# BasicSAMD21.net
KiCad netlist of a schematic drawn in Altium Designer
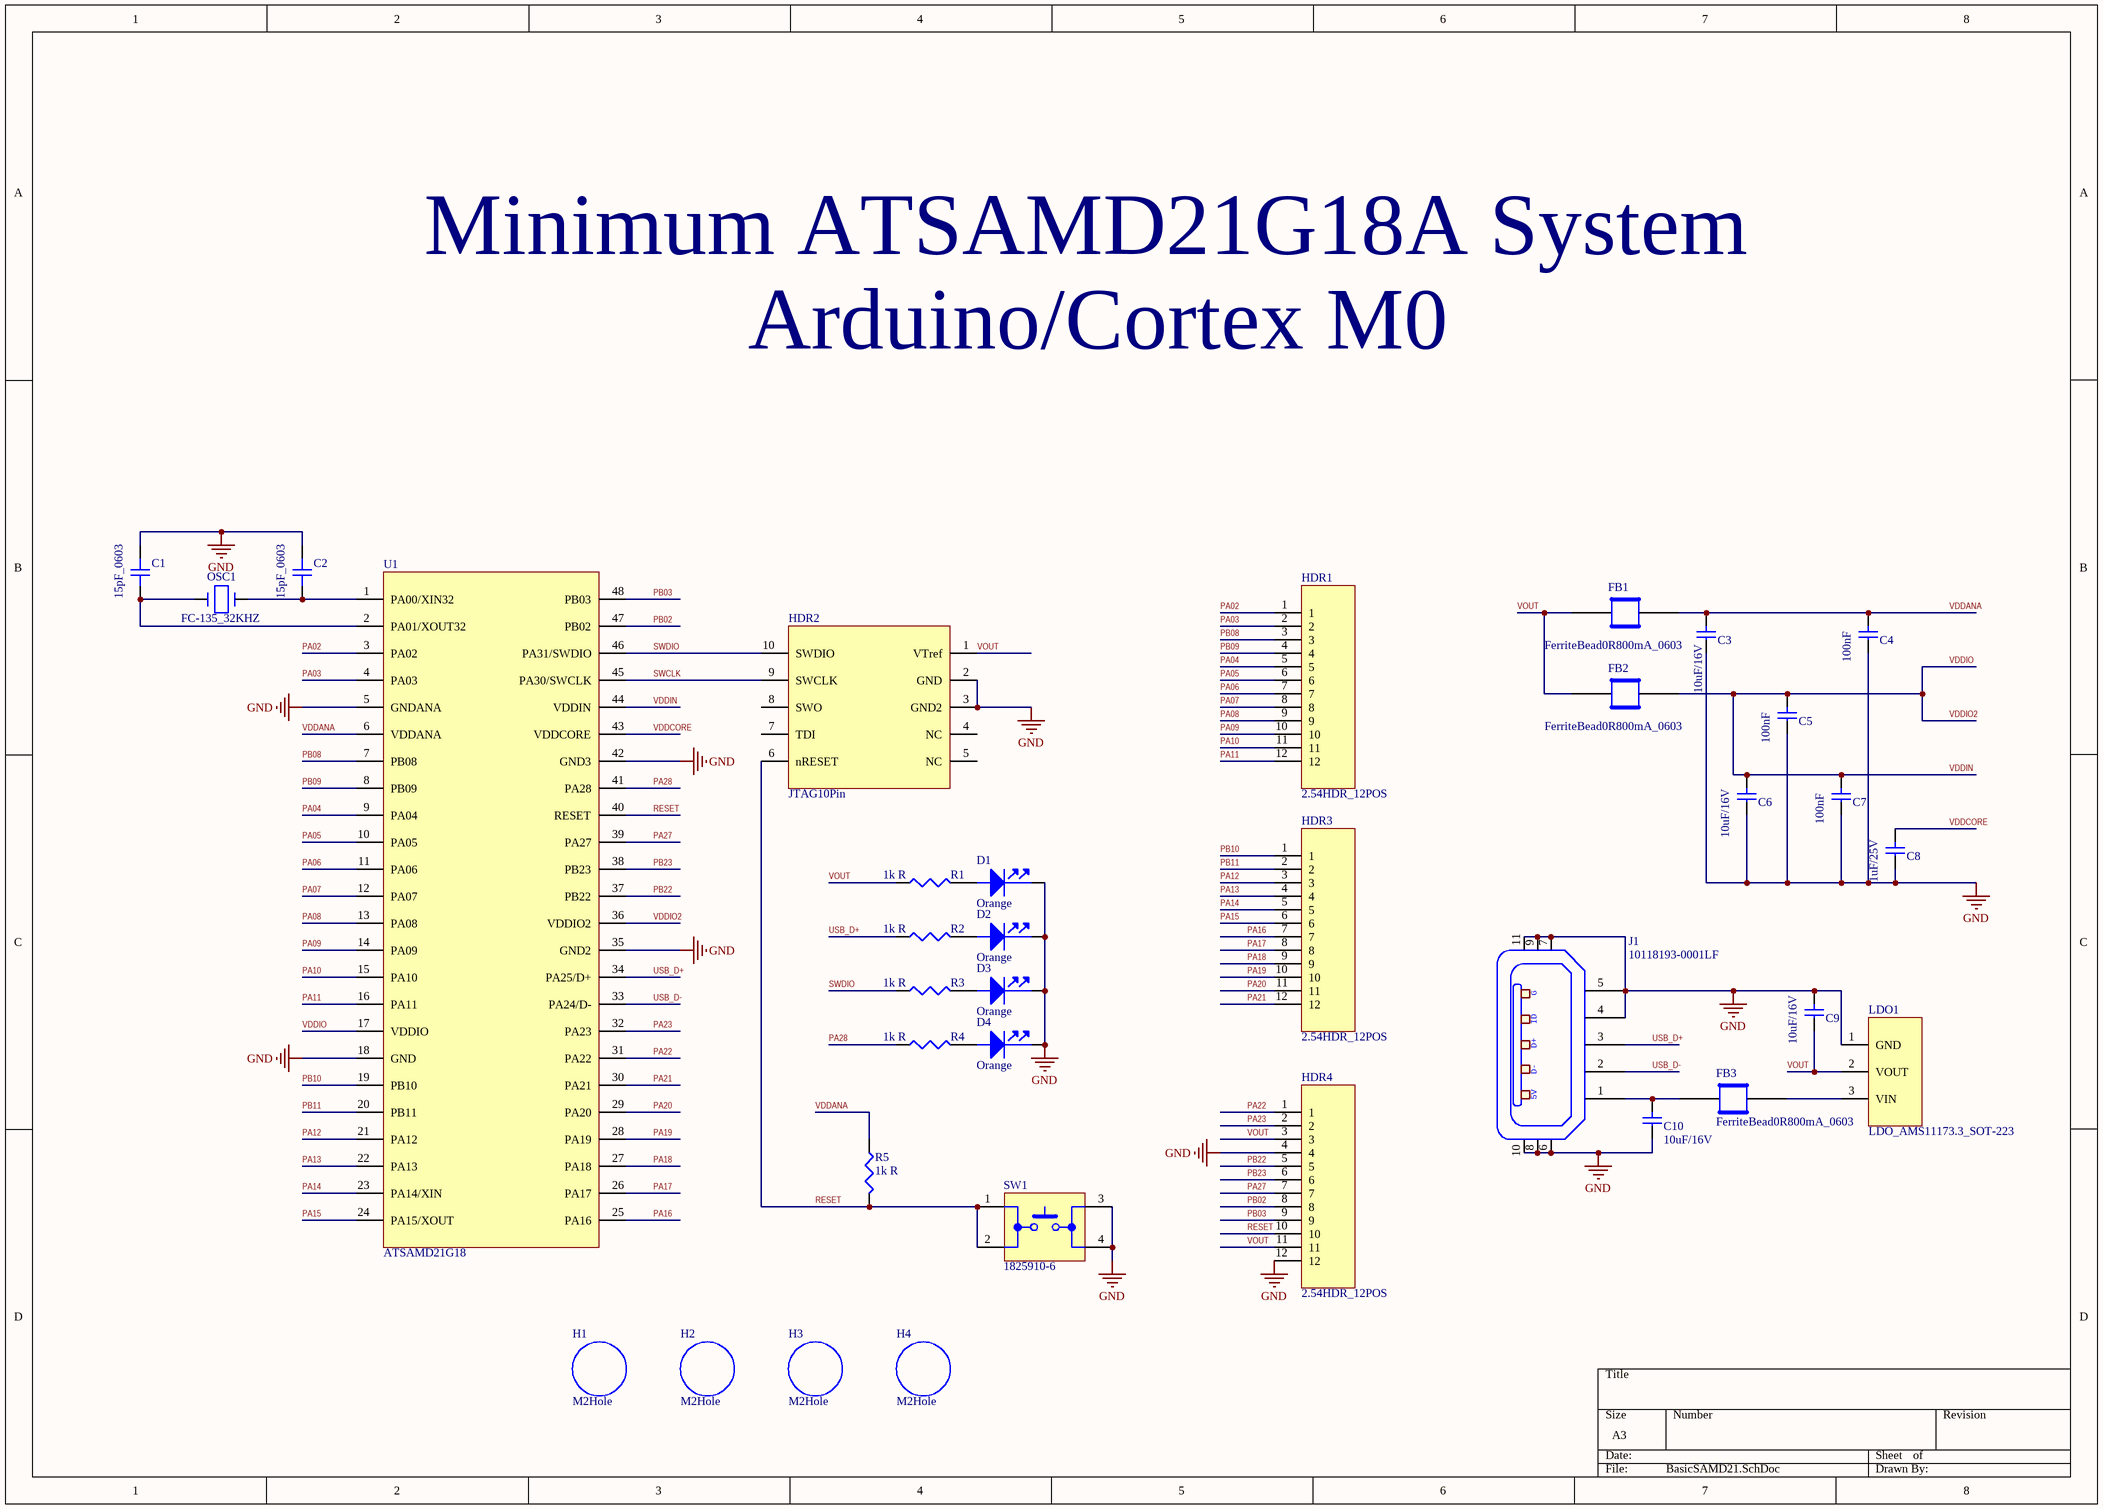
[diagram p0: BasicSAMD21.SchDoc]

(export (version "E")
  (design (tool "Eeschema 10.0.6"))
  (components
    (comp (ref "C1")
      (value "15pF_0603")
      (footprint "C0603")
      (libsource (lib "BasicSAMD21") (part "15pF_0603"))
    )
    (comp (ref "C2")
      (value "15pF_0603")
      (footprint "C0603")
      (libsource (lib "BasicSAMD21") (part "15pF_0603"))
    )
    (comp (ref "C3")
      (value "10uF/16V")
      (footprint "C0805")
      (description "CAP CER 10UF 16V X5R 0805")
      (fields
        (field (name "MANUFACTURER") "TDK Corporation")
        (field (name "MANUFACTURER PART NUMBER") "C2012X5R1C106M125AC")
      )
      (libsource (lib "Schlib1") (part "C2012X5R1C106M125AC"))
    )
    (comp (ref "C4")
      (value "100nF")
      (footprint "C0805")
      (description "CAP CER 0.1UF 50V X7R 0805")
      (fields
        (field (name "MANUFACTURER") "TDK Corporation")
        (field (name "MANUFACTURER PART NUMBER") "C2012X7R1H104K085AA")
      )
      (libsource (lib "Schlib1") (part "C2012X7R1H104K085AA"))
    )
    (comp (ref "C5")
      (value "100nF")
      (footprint "C0805")
      (description "CAP CER 0.1UF 50V X7R 0805")
      (fields
        (field (name "MANUFACTURER") "TDK Corporation")
        (field (name "MANUFACTURER PART NUMBER") "C2012X7R1H104K085AA")
      )
      (libsource (lib "Schlib1") (part "C2012X7R1H104K085AA"))
    )
    (comp (ref "C6")
      (value "10uF/16V")
      (footprint "C0805")
      (description "CAP CER 10UF 16V X5R 0805")
      (fields
        (field (name "MANUFACTURER") "TDK Corporation")
        (field (name "MANUFACTURER PART NUMBER") "C2012X5R1C106M125AC")
      )
      (libsource (lib "Schlib1") (part "C2012X5R1C106M125AC"))
    )
    (comp (ref "C7")
      (value "100nF")
      (footprint "C0805")
      (description "CAP CER 0.1UF 50V X7R 0805")
      (fields
        (field (name "MANUFACTURER") "TDK Corporation")
        (field (name "MANUFACTURER PART NUMBER") "C2012X7R1H104K085AA")
      )
      (libsource (lib "Schlib1") (part "C2012X7R1H104K085AA"))
    )
    (comp (ref "C8")
      (value "1uF/25V")
      (footprint "C0805")
      (description "CAP CER 1UF 25V X5R 0805")
      (fields
        (field (name "MANUFACTURER") "TDK Corporation")
        (field (name "MANUFACTURER PART NUMBER") "C2012X5R1E105K125AA")
      )
      (libsource (lib "Schlib1") (part "C2012X5R1E105K125AA"))
    )
    (comp (ref "C9")
      (value "10uF/16V")
      (footprint "C0805")
      (description "CAP CER 10UF 16V X5R 0805")
      (fields
        (field (name "MANUFACTURER") "TDK Corporation")
        (field (name "MANUFACTURER PART NUMBER") "C2012X5R1C106M125AC")
      )
      (libsource (lib "Schlib1") (part "C2012X5R1C106M125AC"))
    )
    (comp (ref "C10")
      (value "10uF/16V")
      (footprint "C0805")
      (description "CAP CER 10UF 16V X5R 0805")
      (fields
        (field (name "MANUFACTURER") "TDK Corporation")
        (field (name "MANUFACTURER PART NUMBER") "C2012X5R1C106M125AC")
      )
      (libsource (lib "Schlib1") (part "C2012X5R1C106M125AC"))
    )
    (comp (ref "D1")
      (value "Orange")
      (footprint "LED_0603")
      (description "LED ORANGE DIFFUSED 0603 SMD")
      (fields
        (field (name "MANUFACTURER") "OSRAM Opto Semiconductors Inc.")
        (field (name "MANUFACTURER PART NUMBER") "LO L29K-H2K1-24-Z")
      )
      (libsource (lib "Schlib1") (part "LO L29K-H2K1-24-Z"))
    )
    (comp (ref "D2")
      (value "Orange")
      (footprint "LED_0603")
      (description "LED ORANGE DIFFUSED 0603 SMD")
      (fields
        (field (name "MANUFACTURER") "OSRAM Opto Semiconductors Inc.")
        (field (name "MANUFACTURER PART NUMBER") "LO L29K-H2K1-24-Z")
      )
      (libsource (lib "Schlib1") (part "LO L29K-H2K1-24-Z"))
    )
    (comp (ref "D3")
      (value "Orange")
      (footprint "LED_0603")
      (description "LED ORANGE DIFFUSED 0603 SMD")
      (fields
        (field (name "MANUFACTURER") "OSRAM Opto Semiconductors Inc.")
        (field (name "MANUFACTURER PART NUMBER") "LO L29K-H2K1-24-Z")
      )
      (libsource (lib "Schlib1") (part "LO L29K-H2K1-24-Z"))
    )
    (comp (ref "D4")
      (value "Orange")
      (footprint "LED_0603")
      (description "LED ORANGE DIFFUSED 0603 SMD")
      (fields
        (field (name "MANUFACTURER") "OSRAM Opto Semiconductors Inc.")
        (field (name "MANUFACTURER PART NUMBER") "LO L29K-H2K1-24-Z")
      )
      (libsource (lib "Schlib1") (part "LO L29K-H2K1-24-Z"))
    )
    (comp (ref "FB1")
      (value "FerriteBead0R800mA_0603")
      (footprint "C0603")
      (libsource (lib "BasicSAMD21") (part "FerriteBead0R800mA_0603"))
    )
    (comp (ref "FB2")
      (value "FerriteBead0R800mA_0603")
      (footprint "C0603")
      (libsource (lib "BasicSAMD21") (part "FerriteBead0R800mA_0603"))
    )
    (comp (ref "FB3")
      (value "FerriteBead0R800mA_0603")
      (footprint "C0603")
      (libsource (lib "BasicSAMD21") (part "FerriteBead0R800mA_0603"))
    )
    (comp (ref "H1") (value "M2Hole") (footprint "M2Hole") (libsource (lib "BasicSAMD21") (part "M2Hole")))
    (comp (ref "H2") (value "M2Hole") (footprint "M2Hole") (libsource (lib "BasicSAMD21") (part "M2Hole")))
    (comp (ref "H3") (value "M2Hole") (footprint "M2Hole") (libsource (lib "BasicSAMD21") (part "M2Hole")))
    (comp (ref "H4") (value "M2Hole") (footprint "M2Hole") (libsource (lib "BasicSAMD21") (part "M2Hole")))
    (comp (ref "HDR1")
      (value "2.54HDR_12POS")
      (footprint "DIP12")
      (libsource (lib "BasicSAMD21") (part "2.54HDR_12POS"))
    )
    (comp (ref "HDR2")
      (value "JTAG10Pin")
      (footprint "JTAG10")
      (libsource (lib "BasicSAMD21") (part "JTAG_10Pin"))
    )
    (comp (ref "HDR3")
      (value "2.54HDR_12POS")
      (footprint "DIP12")
      (libsource (lib "BasicSAMD21") (part "2.54HDR_12POS"))
    )
    (comp (ref "HDR4")
      (value "2.54HDR_12POS")
      (footprint "DIP12")
      (libsource (lib "BasicSAMD21") (part "2.54HDR_12POS"))
    )
    (comp (ref "J1")
      (value "10118193-0001LF")
      (footprint "10118193")
      (description "CONN USB MICRO B RECPT SMT R/A")
      (fields (field (name "MANUFACTURER") "Amphenol FCI"))
      (libsource (lib "Schlib1") (part "10118193-0001LF"))
    )
    (comp (ref "LDO1")
      (value "LDO_AMS11173.3_SOT-223")
      (footprint "SOT223")
      (libsource (lib "BasicSAMD21") (part "LDO_AMS11173.3_SOT-223"))
    )
    (comp (ref "OSC1")
      (value "FC-135_32KHZ")
      (footprint "FC-135")
      (description "32.768kHz ±20ppm Crystal 12.5pF 50 kOhm -40°C ~ 85°C  Surface Mount 2-SMD, No Lead (DFN, LCC)")
      (fields
        (field (name "MANUFACTURER") "Epson")
        (field (name "MANUFACTURER PART NUMBER") "FC-135R32.7680KA-A3")
      )
      (libsource (lib "BasicSAMD21") (part "FC-135R32.7680KA-A3"))
    )
    (comp (ref "R1")
      (value "1k R")
      (footprint "R0805")
      (description "RES SMD 1K OHM 1% 1/8W 0805")
      (fields
        (field (name "MANUFACTURER") "Yageo")
        (field (name "MANUFACTURER PART NUMBER") "RC0805FR-071KL")
      )
      (libsource (lib "Schlib1") (part "RC0805FR-071KL"))
    )
    (comp (ref "R2")
      (value "1k R")
      (footprint "R0805")
      (description "RES SMD 1K OHM 1% 1/8W 0805")
      (fields
        (field (name "MANUFACTURER") "Yageo")
        (field (name "MANUFACTURER PART NUMBER") "RC0805FR-071KL")
      )
      (libsource (lib "Schlib1") (part "RC0805FR-071KL"))
    )
    (comp (ref "R3")
      (value "1k R")
      (footprint "R0805")
      (description "RES SMD 1K OHM 1% 1/8W 0805")
      (fields
        (field (name "MANUFACTURER") "Yageo")
        (field (name "MANUFACTURER PART NUMBER") "RC0805FR-071KL")
      )
      (libsource (lib "Schlib1") (part "RC0805FR-071KL"))
    )
    (comp (ref "R4")
      (value "1k R")
      (footprint "R0805")
      (description "RES SMD 1K OHM 1% 1/8W 0805")
      (fields
        (field (name "MANUFACTURER") "Yageo")
        (field (name "MANUFACTURER PART NUMBER") "RC0805FR-071KL")
      )
      (libsource (lib "Schlib1") (part "RC0805FR-071KL"))
    )
    (comp (ref "R5")
      (value "1k R")
      (footprint "R0805")
      (description "RES SMD 1K OHM 1% 1/8W 0805")
      (fields
        (field (name "MANUFACTURER") "Yageo")
        (field (name "MANUFACTURER PART NUMBER") "RC0805FR-071KL")
      )
      (libsource (lib "Schlib1") (part "RC0805FR-071KL"))
    )
    (comp (ref "SW1")
      (value "1825910-6")
      (footprint "1825910-6")
      (description "SWITCH TACTILE SPST-NO 0.05A 24V")
      (fields (field (name "MANUFACTURER") "TE Connectivity ALCOSWITCH Switches"))
      (libsource (lib "Schlib1") (part "1825910-6"))
    )
    (comp (ref "U1")
      (value "ATSAMD21G18")
      (footprint "TQFP48")
      (description "IC MCU 32BIT 256KB FLASH 48TQFP")
      (fields
        (field (name "MANUFACTURER") "Microchip")
        (field (name "MANUFACTURER PART NUMBER") "ATSAMD21G18A-AUT")
      )
      (libsource (lib "BasicSAMD21") (part "ATSAMD21G18A-AUT"))
    )
  )
  (nets
    (net (code "1") (name "/PA02") (class "Default")
      (node (ref "HDR1") (pin "1") (pinfunction "1_1") (pintype "passive"))
      (node (ref "U1") (pin "3") (pinfunction "PA02_3") (pintype "passive"))
    )
    (net (code "2") (name "/PA03") (class "Default")
      (node (ref "HDR1") (pin "2") (pinfunction "2_2") (pintype "passive"))
      (node (ref "U1") (pin "4") (pinfunction "PA03_4") (pintype "passive"))
    )
    (net (code "3") (name "/PA04") (class "Default")
      (node (ref "HDR1") (pin "5") (pinfunction "5_5") (pintype "passive"))
      (node (ref "U1") (pin "9") (pinfunction "PA04_9") (pintype "passive"))
    )
    (net (code "4") (name "/PA05") (class "Default")
      (node (ref "HDR1") (pin "6") (pinfunction "6_6") (pintype "passive"))
      (node (ref "U1") (pin "10") (pinfunction "PA05_10") (pintype "passive"))
    )
    (net (code "5") (name "/PA06") (class "Default")
      (node (ref "HDR1") (pin "7") (pinfunction "7_7") (pintype "passive"))
      (node (ref "U1") (pin "11") (pinfunction "PA06_11") (pintype "passive"))
    )
    (net (code "6") (name "/PA07") (class "Default")
      (node (ref "HDR1") (pin "8") (pinfunction "8_8") (pintype "passive"))
      (node (ref "U1") (pin "12") (pinfunction "PA07_12") (pintype "passive"))
    )
    (net (code "7") (name "/PA08") (class "Default")
      (node (ref "HDR1") (pin "9") (pinfunction "9_9") (pintype "passive"))
      (node (ref "U1") (pin "13") (pinfunction "PA08_13") (pintype "passive"))
    )
    (net (code "8") (name "/PA09") (class "Default")
      (node (ref "HDR1") (pin "10") (pinfunction "10_10") (pintype "passive"))
      (node (ref "U1") (pin "14") (pinfunction "PA09_14") (pintype "passive"))
    )
    (net (code "9") (name "/PA10") (class "Default")
      (node (ref "HDR1") (pin "11") (pinfunction "11_11") (pintype "passive"))
      (node (ref "U1") (pin "15") (pinfunction "PA10_15") (pintype "passive"))
    )
    (net (code "10") (name "/PA11") (class "Default")
      (node (ref "HDR1") (pin "12") (pinfunction "12_12") (pintype "passive"))
      (node (ref "U1") (pin "16") (pinfunction "PA11_16") (pintype "passive"))
    )
    (net (code "11") (name "/PA12") (class "Default")
      (node (ref "HDR3") (pin "3") (pinfunction "3_3") (pintype "passive"))
      (node (ref "U1") (pin "21") (pinfunction "PA12_21") (pintype "passive"))
    )
    (net (code "12") (name "/PA13") (class "Default")
      (node (ref "HDR3") (pin "4") (pinfunction "4_4") (pintype "passive"))
      (node (ref "U1") (pin "22") (pinfunction "PA13_22") (pintype "passive"))
    )
    (net (code "13") (name "/PA14") (class "Default")
      (node (ref "HDR3") (pin "5") (pinfunction "5_5") (pintype "passive"))
      (node (ref "U1") (pin "23") (pinfunction "PA14/XIN_23") (pintype "passive"))
    )
    (net (code "14") (name "/PA15") (class "Default")
      (node (ref "HDR3") (pin "6") (pinfunction "6_6") (pintype "passive"))
      (node (ref "U1") (pin "24") (pinfunction "PA15/XOUT_24") (pintype "passive"))
    )
    (net (code "15") (name "/PA16") (class "Default")
      (node (ref "HDR3") (pin "7") (pinfunction "7_7") (pintype "passive"))
      (node (ref "U1") (pin "25") (pinfunction "PA16_25") (pintype "passive"))
    )
    (net (code "16") (name "/PA17") (class "Default")
      (node (ref "HDR3") (pin "8") (pinfunction "8_8") (pintype "passive"))
      (node (ref "U1") (pin "26") (pinfunction "PA17_26") (pintype "passive"))
    )
    (net (code "17") (name "/PA18") (class "Default")
      (node (ref "HDR3") (pin "9") (pinfunction "9_9") (pintype "passive"))
      (node (ref "U1") (pin "27") (pinfunction "PA18_27") (pintype "passive"))
    )
    (net (code "18") (name "/PA19") (class "Default")
      (node (ref "HDR3") (pin "10") (pinfunction "10_10") (pintype "passive"))
      (node (ref "U1") (pin "28") (pinfunction "PA19_28") (pintype "passive"))
    )
    (net (code "19") (name "/PA20") (class "Default")
      (node (ref "HDR3") (pin "11") (pinfunction "11_11") (pintype "passive"))
      (node (ref "U1") (pin "29") (pinfunction "PA20_29") (pintype "passive"))
    )
    (net (code "20") (name "/PA21") (class "Default")
      (node (ref "HDR3") (pin "12") (pinfunction "12_12") (pintype "passive"))
      (node (ref "U1") (pin "30") (pinfunction "PA21_30") (pintype "passive"))
    )
    (net (code "21") (name "/PA22") (class "Default")
      (node (ref "HDR4") (pin "1") (pinfunction "1_1") (pintype "passive"))
      (node (ref "U1") (pin "31") (pinfunction "PA22_31") (pintype "passive"))
    )
    (net (code "22") (name "/PA23") (class "Default")
      (node (ref "HDR4") (pin "2") (pinfunction "2_2") (pintype "passive"))
      (node (ref "U1") (pin "32") (pinfunction "PA23_32") (pintype "passive"))
    )
    (net (code "23") (name "/PA27") (class "Default")
      (node (ref "HDR4") (pin "7") (pinfunction "7_7") (pintype "passive"))
      (node (ref "U1") (pin "39") (pinfunction "PA27_39") (pintype "passive"))
    )
    (net (code "24") (name "/PA28") (class "Default")
      (node (ref "R4") (pin "1") (pinfunction "1_1") (pintype "passive"))
      (node (ref "U1") (pin "41") (pinfunction "PA28_41") (pintype "passive"))
    )
    (net (code "25") (name "/PB02") (class "Default")
      (node (ref "HDR4") (pin "8") (pinfunction "8_8") (pintype "passive"))
      (node (ref "U1") (pin "47") (pinfunction "PB02_47") (pintype "passive"))
    )
    (net (code "26") (name "/PB03") (class "Default")
      (node (ref "HDR4") (pin "9") (pinfunction "9_9") (pintype "passive"))
      (node (ref "U1") (pin "48") (pinfunction "PB03_48") (pintype "passive"))
    )
    (net (code "27") (name "/PB08") (class "Default")
      (node (ref "HDR1") (pin "3") (pinfunction "3_3") (pintype "passive"))
      (node (ref "U1") (pin "7") (pinfunction "PB08_7") (pintype "passive"))
    )
    (net (code "28") (name "/PB09") (class "Default")
      (node (ref "HDR1") (pin "4") (pinfunction "4_4") (pintype "passive"))
      (node (ref "U1") (pin "8") (pinfunction "PB09_8") (pintype "passive"))
    )
    (net (code "29") (name "/PB10") (class "Default")
      (node (ref "HDR3") (pin "1") (pinfunction "1_1") (pintype "passive"))
      (node (ref "U1") (pin "19") (pinfunction "PB10_19") (pintype "passive"))
    )
    (net (code "30") (name "/PB11") (class "Default")
      (node (ref "HDR3") (pin "2") (pinfunction "2_2") (pintype "passive"))
      (node (ref "U1") (pin "20") (pinfunction "PB11_20") (pintype "passive"))
    )
    (net (code "31") (name "/PB22") (class "Default")
      (node (ref "HDR4") (pin "5") (pinfunction "5_5") (pintype "passive"))
      (node (ref "U1") (pin "37") (pinfunction "PB22_37") (pintype "passive"))
    )
    (net (code "32") (name "/PB23") (class "Default")
      (node (ref "HDR4") (pin "6") (pinfunction "6_6") (pintype "passive"))
      (node (ref "U1") (pin "38") (pinfunction "PB23_38") (pintype "passive"))
    )
    (net (code "33") (name "/RESET") (class "Default")
      (node (ref "HDR2") (pin "6") (pinfunction "nRESET_6") (pintype "passive"))
      (node (ref "HDR4") (pin "10") (pinfunction "10_10") (pintype "passive"))
      (node (ref "R5") (pin "2") (pinfunction "2_2") (pintype "passive"))
      (node (ref "SW1") (pin "1") (pinfunction "1_1") (pintype "passive"))
      (node (ref "SW1") (pin "2") (pinfunction "2_2") (pintype "passive"))
      (node (ref "U1") (pin "40") (pinfunction "RESET_40") (pintype "passive"))
    )
    (net (code "34") (name "/SWCLK") (class "Default")
      (node (ref "HDR2") (pin "9") (pinfunction "SWCLK_9") (pintype "passive"))
      (node (ref "U1") (pin "45") (pinfunction "PA30/SWCLK_45") (pintype "passive"))
    )
    (net (code "35") (name "/SWDIO") (class "Default")
      (node (ref "HDR2") (pin "10") (pinfunction "SWDIO_10") (pintype "passive"))
      (node (ref "R3") (pin "1") (pinfunction "1_1") (pintype "passive"))
      (node (ref "U1") (pin "46") (pinfunction "PA31/SWDIO_46") (pintype "passive"))
    )
    (net (code "36") (name "/USB_D+") (class "Default")
      (node (ref "J1") (pin "3") (pinfunction "3_3") (pintype "passive"))
      (node (ref "R2") (pin "1") (pinfunction "1_1") (pintype "passive"))
      (node (ref "U1") (pin "34") (pinfunction "PA25/D+_34") (pintype "passive"))
    )
    (net (code "37") (name "/USB_D-") (class "Default")
      (node (ref "J1") (pin "2") (pinfunction "2_2") (pintype "passive"))
      (node (ref "U1") (pin "33") (pinfunction "PA24/D-_33") (pintype "passive"))
    )
    (net (code "38") (name "/VDDANA") (class "Default")
      (node (ref "C3") (pin "2") (pinfunction "2_2") (pintype "passive"))
      (node (ref "C4") (pin "2") (pinfunction "2_2") (pintype "passive"))
      (node (ref "FB1") (pin "2") (pinfunction "2_2") (pintype "passive"))
      (node (ref "R5") (pin "1") (pinfunction "1_1") (pintype "passive"))
      (node (ref "U1") (pin "6") (pinfunction "VDDANA_6") (pintype "passive"))
    )
    (net (code "39") (name "/VDDCORE") (class "Default")
      (node (ref "C8") (pin "2") (pinfunction "2_2") (pintype "passive"))
      (node (ref "U1") (pin "43") (pinfunction "VDDCORE_43") (pintype "passive"))
    )
    (net (code "40") (name "/VDDIN") (class "Default")
      (node (ref "C5") (pin "2") (pinfunction "2_2") (pintype "passive"))
      (node (ref "C6") (pin "2") (pinfunction "2_2") (pintype "passive"))
      (node (ref "C7") (pin "2") (pinfunction "2_2") (pintype "passive"))
      (node (ref "FB2") (pin "2") (pinfunction "2_2") (pintype "passive"))
      (node (ref "U1") (pin "17") (pinfunction "VDDIO_17") (pintype "passive"))
      (node (ref "U1") (pin "36") (pinfunction "VDDIO2_36") (pintype "passive"))
      (node (ref "U1") (pin "44") (pinfunction "VDDIN_44") (pintype "passive"))
    )
    (net (code "41") (name "/VOUT") (class "Default")
      (node (ref "C9") (pin "1") (pinfunction "1_1") (pintype "passive"))
      (node (ref "FB1") (pin "1") (pinfunction "1_1") (pintype "passive"))
      (node (ref "FB2") (pin "1") (pinfunction "1_1") (pintype "passive"))
      (node (ref "HDR2") (pin "1") (pinfunction "VTref_1") (pintype "passive"))
      (node (ref "HDR4") (pin "11") (pinfunction "11_11") (pintype "passive"))
      (node (ref "HDR4") (pin "3") (pinfunction "3_3") (pintype "passive"))
      (node (ref "LDO1") (pin "2") (pinfunction "VOUT_2") (pintype "passive"))
      (node (ref "R1") (pin "1") (pinfunction "1_1") (pintype "passive"))
    )
    (net (code "42") (name "GND") (class "Default")
      (node (ref "C1") (pin "2") (pinfunction "2_2") (pintype "passive"))
      (node (ref "C10") (pin "1") (pinfunction "1_1") (pintype "passive"))
      (node (ref "C2") (pin "2") (pinfunction "2_2") (pintype "passive"))
      (node (ref "C3") (pin "1") (pinfunction "1_1") (pintype "passive"))
      (node (ref "C4") (pin "1") (pinfunction "1_1") (pintype "passive"))
      (node (ref "C5") (pin "1") (pinfunction "1_1") (pintype "passive"))
      (node (ref "C6") (pin "1") (pinfunction "1_1") (pintype "passive"))
      (node (ref "C7") (pin "1") (pinfunction "1_1") (pintype "passive"))
      (node (ref "C8") (pin "1") (pinfunction "1_1") (pintype "passive"))
      (node (ref "C9") (pin "2") (pinfunction "2_2") (pintype "passive"))
      (node (ref "D1") (pin "1") (pinfunction "Cathode_1") (pintype "passive"))
      (node (ref "D2") (pin "1") (pinfunction "Cathode_1") (pintype "passive"))
      (node (ref "D3") (pin "1") (pinfunction "Cathode_1") (pintype "passive"))
      (node (ref "D4") (pin "1") (pinfunction "Cathode_1") (pintype "passive"))
      (node (ref "HDR2") (pin "2") (pinfunction "GND_2") (pintype "passive"))
      (node (ref "HDR2") (pin "3") (pinfunction "GND2_3") (pintype "passive"))
      (node (ref "HDR4") (pin "12") (pinfunction "12_12") (pintype "passive"))
      (node (ref "HDR4") (pin "4") (pinfunction "4_4") (pintype "passive"))
      (node (ref "J1") (pin "10") (pinfunction "10_10") (pintype "passive"))
      (node (ref "J1") (pin "11") (pinfunction "11_11") (pintype "passive"))
      (node (ref "J1") (pin "4") (pinfunction "4_4") (pintype "passive"))
      (node (ref "J1") (pin "5") (pinfunction "5_5") (pintype "passive"))
      (node (ref "J1") (pin "6") (pinfunction "6_6") (pintype "passive"))
      (node (ref "J1") (pin "7") (pinfunction "7_7") (pintype "passive"))
      (node (ref "J1") (pin "8") (pinfunction "8_8") (pintype "passive"))
      (node (ref "J1") (pin "9") (pinfunction "9_9") (pintype "passive"))
      (node (ref "LDO1") (pin "1") (pinfunction "GND_1") (pintype "passive"))
      (node (ref "SW1") (pin "3") (pinfunction "3_3") (pintype "passive"))
      (node (ref "SW1") (pin "4") (pinfunction "4_4") (pintype "passive"))
      (node (ref "U1") (pin "18") (pinfunction "GND_18") (pintype "passive"))
      (node (ref "U1") (pin "35") (pinfunction "GND2_35") (pintype "passive"))
      (node (ref "U1") (pin "42") (pinfunction "GND3_42") (pintype "passive"))
      (node (ref "U1") (pin "5") (pinfunction "GNDANA_5") (pintype "passive"))
    )
    (net (code "43") (name "Net-(C10-Pad2)") (class "Default")
      (node (ref "C10") (pin "2") (pinfunction "2_2") (pintype "passive"))
      (node (ref "FB3") (pin "1") (pinfunction "1_1") (pintype "passive"))
      (node (ref "J1") (pin "1") (pinfunction "1_1") (pintype "passive"))
    )
    (net (code "44") (name "Net-(D1-Anode)") (class "Default")
      (node (ref "D1") (pin "2") (pinfunction "Anode_2") (pintype "passive"))
      (node (ref "R1") (pin "2") (pinfunction "2_2") (pintype "passive"))
    )
    (net (code "45") (name "Net-(D2-Anode)") (class "Default")
      (node (ref "D2") (pin "2") (pinfunction "Anode_2") (pintype "passive"))
      (node (ref "R2") (pin "2") (pinfunction "2_2") (pintype "passive"))
    )
    (net (code "46") (name "Net-(D3-Anode)") (class "Default")
      (node (ref "D3") (pin "2") (pinfunction "Anode_2") (pintype "passive"))
      (node (ref "R3") (pin "2") (pinfunction "2_2") (pintype "passive"))
    )
    (net (code "47") (name "Net-(D4-Anode)") (class "Default")
      (node (ref "D4") (pin "2") (pinfunction "Anode_2") (pintype "passive"))
      (node (ref "R4") (pin "2") (pinfunction "2_2") (pintype "passive"))
    )
    (net (code "48") (name "Net-(LDO1-VIN)") (class "Default")
      (node (ref "FB3") (pin "2") (pinfunction "2_2") (pintype "passive"))
      (node (ref "LDO1") (pin "3") (pinfunction "VIN_3") (pintype "passive"))
    )
    (net (code "49") (name "Net-(U1-PA00{slash}XIN32)") (class "Default")
      (node (ref "C2") (pin "1") (pinfunction "1_1") (pintype "passive"))
      (node (ref "OSC1") (pin "1") (pinfunction "1_1") (pintype "passive"))
      (node (ref "U1") (pin "1") (pinfunction "PA00/XIN32_1") (pintype "passive"))
    )
    (net (code "50") (name "Net-(U1-PA01{slash}XOUT32)") (class "Default")
      (node (ref "C1") (pin "1") (pinfunction "1_1") (pintype "passive"))
      (node (ref "OSC1") (pin "2") (pinfunction "2_2") (pintype "passive"))
      (node (ref "U1") (pin "2") (pinfunction "PA01/XOUT32_2") (pintype "passive"))
    )
    (net (code "51") (name "unconnected-(HDR2-NC-Pad4)") (class "Default")
      (node (ref "HDR2") (pin "4") (pinfunction "NC_4") (pintype "passive"))
    )
    (net (code "52") (name "unconnected-(HDR2-NC-Pad5)") (class "Default")
      (node (ref "HDR2") (pin "5") (pinfunction "NC_5") (pintype "passive"))
    )
    (net (code "53") (name "unconnected-(HDR2-SWO-Pad8)") (class "Default")
      (node (ref "HDR2") (pin "8") (pinfunction "SWO_8") (pintype "passive"))
    )
    (net (code "54") (name "unconnected-(HDR2-TDI-Pad7)") (class "Default")
      (node (ref "HDR2") (pin "7") (pinfunction "TDI_7") (pintype "passive"))
    )
  )
)
